# USB_INT.net
KiCad netlist of a schematic drawn in Altium Designer
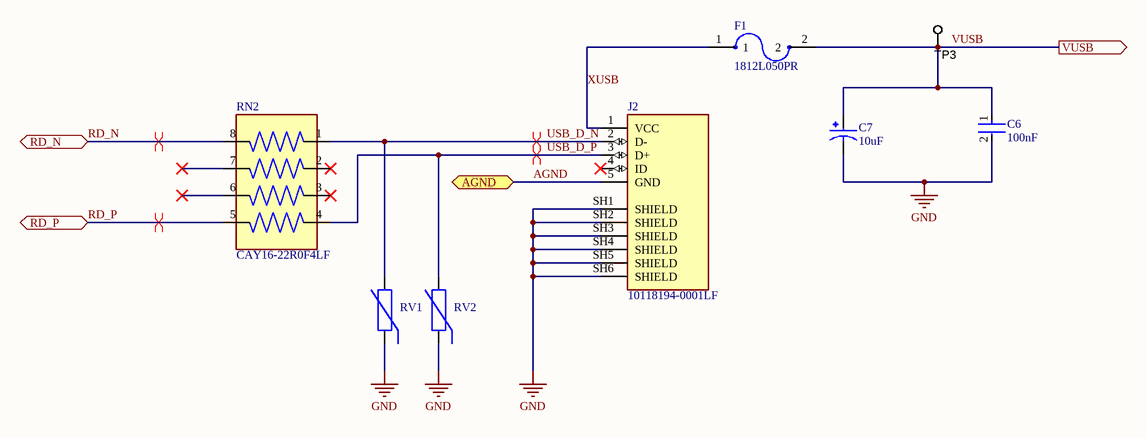
[diagram p0: USB_INT.SchDoc]

(export (version "E")
  (design (tool "Eeschema 10.0.6"))
  (components
    (comp (ref "C6")
      (value "100nF")
      (footprint "FP-GRT31C-0_2-MFG")
      (description "Multi-Layer Ceramic Capacitor 100nF 50V C0G ±1% 1206 Emboss T/R")
      (libsource (lib "Altium Content Vault") (part "02cd4be3c70576c341d710602a673aa"))
    )
    (comp (ref "C7")
      (value "10uF")
      (footprint "CAP_EEEHB1C100AR")
      (description "10ÂµF 16V Aluminum Electrolytic Capacitors Radial, Can - SMD 2000 Hrs @ 105Â°C")
      (fields (field (name "MP") "EEE-HB1C100AR") (field (name "MF") "Panasonic"))
      (libsource (lib "RFID") (part "EEEHB1C100AR"))
    )
    (comp (ref "F1")
      (value "1812L050PR")
      (footprint "FUSM4632X75")
      (description "Polymeric PTC Resettable Fuse 15V 500mA Ih Surface Mount 1812 (4532 Metric), Concave")
      (fields (field (name "MF") "Littelfuse Inc."))
      (libsource (lib "RFID") (part "1812L050PR"))
    )
    (comp (ref "J2")
      (value "10118194-0001LF")
      (footprint "AMPHENOL_10118194-0001LF")
      (description "Micro USB, Input Output Connectors, B TYPE RECEPTACLE with flange")
      (fields (field (name "MF") "Amphenol ICC"))
      (libsource (lib "RFID") (part "10118194-0001LF"))
    )
    (comp (ref "RN2")
      (value "CAY16-22R0F4LF")
      (footprint "RESCAF80P320X160X60-8N")
      (fields (field (name "MF") "Bourns"))
      (libsource (lib "RFID") (part "CAY16-22R0F4LF"))
    )
    (comp (ref "RV1")
      (value "CG0603MLC-05E")
      (footprint "BOUR-CG0603-2_V")
      (description "ESD Protector, 5 V Supply, -40 to 85 degC, 1.6 x 0.8 x 0.55 mm SMD, RoHS, Tape and Reel")
      (fields (field (name "MANUFACTURER") "Bourns"))
      (libsource (lib "Altium Content Vault") (part "BOUR-VSR-2"))
    )
    (comp (ref "RV2")
      (value "CG0603MLC-05E")
      (footprint "BOUR-CG0603-2_V")
      (description "ESD Protector, 5 V Supply, -40 to 85 degC, 1.6 x 0.8 x 0.55 mm SMD, RoHS, Tape and Reel")
      (fields (field (name "MANUFACTURER") "Bourns"))
      (libsource (lib "Altium Content Vault") (part "BOUR-VSR-2"))
    )
    (comp (ref "TP3")
      (value "TESTPOINT_SMD_C1")
      (footprint "TPSMD_C60")
      (description "TEST POINT")
      (fields (field (name "MANF") "MANF") (field (name "MANF_P#") "MANF_P#"))
      (libsource (lib "RFID") (part "TESTPOINT_SMD_C1"))
    )
  )
  (nets
    (net (code "1") (name "/AGND") (class "Default")
      (node (ref "J2") (pin "5") (pinfunction "GND_5") (pintype "passive"))
    )
    (net (code "2") (name "/RD_N") (class "Default")
      (node (ref "RN2") (pin "8") (pinfunction "8_8") (pintype "passive"))
    )
    (net (code "3") (name "/RD_P") (class "Default")
      (node (ref "RN2") (pin "5") (pinfunction "5_5") (pintype "passive"))
    )
    (net (code "4") (name "/USB_D_N") (class "Default")
      (node (ref "J2") (pin "2") (pinfunction "D-_2") (pintype "bidirectional"))
      (node (ref "RN2") (pin "1") (pinfunction "1_1") (pintype "passive"))
      (node (ref "RV1") (pin "2") (pinfunction "2_2") (pintype "passive"))
    )
    (net (code "5") (name "/USB_D_P") (class "Default")
      (node (ref "J2") (pin "3") (pinfunction "D+_3") (pintype "bidirectional"))
      (node (ref "RN2") (pin "4") (pinfunction "4_4") (pintype "passive"))
      (node (ref "RV2") (pin "2") (pinfunction "2_2") (pintype "passive"))
    )
    (net (code "6") (name "/VUSB") (class "Default")
      (node (ref "C6") (pin "1") (pinfunction "1_1") (pintype "passive"))
      (node (ref "C7") (pin "1") (pinfunction "1_1") (pintype "passive"))
      (node (ref "F1") (pin "2") (pinfunction "2_2") (pintype "passive"))
      (node (ref "TP3") (pin "1") (pinfunction "1_1") (pintype "passive"))
    )
    (net (code "7") (name "/XUSB") (class "Default")
      (node (ref "F1") (pin "1") (pinfunction "1_1") (pintype "passive"))
      (node (ref "J2") (pin "1") (pinfunction "VCC_1") (pintype "power_in"))
    )
    (net (code "8") (name "GND") (class "Default")
      (node (ref "C6") (pin "2") (pinfunction "2_2") (pintype "passive"))
      (node (ref "C7") (pin "2") (pinfunction "2_2") (pintype "passive"))
      (node (ref "J2") (pin "SH1") (pinfunction "SHIELD_SH1") (pintype "passive"))
      (node (ref "J2") (pin "SH2") (pinfunction "SHIELD_SH2") (pintype "passive"))
      (node (ref "J2") (pin "SH3") (pinfunction "SHIELD_SH3") (pintype "passive"))
      (node (ref "J2") (pin "SH4") (pinfunction "SHIELD_SH4") (pintype "passive"))
      (node (ref "J2") (pin "SH5") (pinfunction "SHIELD_SH5") (pintype "passive"))
      (node (ref "J2") (pin "SH6") (pinfunction "SHIELD_SH6") (pintype "passive"))
      (node (ref "RV1") (pin "1") (pinfunction "1_1") (pintype "passive"))
      (node (ref "RV2") (pin "1") (pinfunction "1_1") (pintype "passive"))
    )
    (net (code "9") (name "unconnected-(J2-ID-Pad4)") (class "Default")
      (node (ref "J2") (pin "4") (pinfunction "ID_4") (pintype "bidirectional+no_connect"))
    )
    (net (code "10") (name "unconnected-(RN2-Pad2)") (class "Default")
      (node (ref "RN2") (pin "2") (pinfunction "2_2") (pintype "passive+no_connect"))
    )
    (net (code "11") (name "unconnected-(RN2-Pad3)") (class "Default")
      (node (ref "RN2") (pin "3") (pinfunction "3_3") (pintype "passive+no_connect"))
    )
    (net (code "12") (name "unconnected-(RN2-Pad6)") (class "Default")
      (node (ref "RN2") (pin "6") (pinfunction "6_6") (pintype "passive+no_connect"))
    )
    (net (code "13") (name "unconnected-(RN2-Pad7)") (class "Default")
      (node (ref "RN2") (pin "7") (pinfunction "7_7") (pintype "passive+no_connect"))
    )
  )
)
